# decoupling.net
KiCad netlist of a schematic drawn in Altium Designer
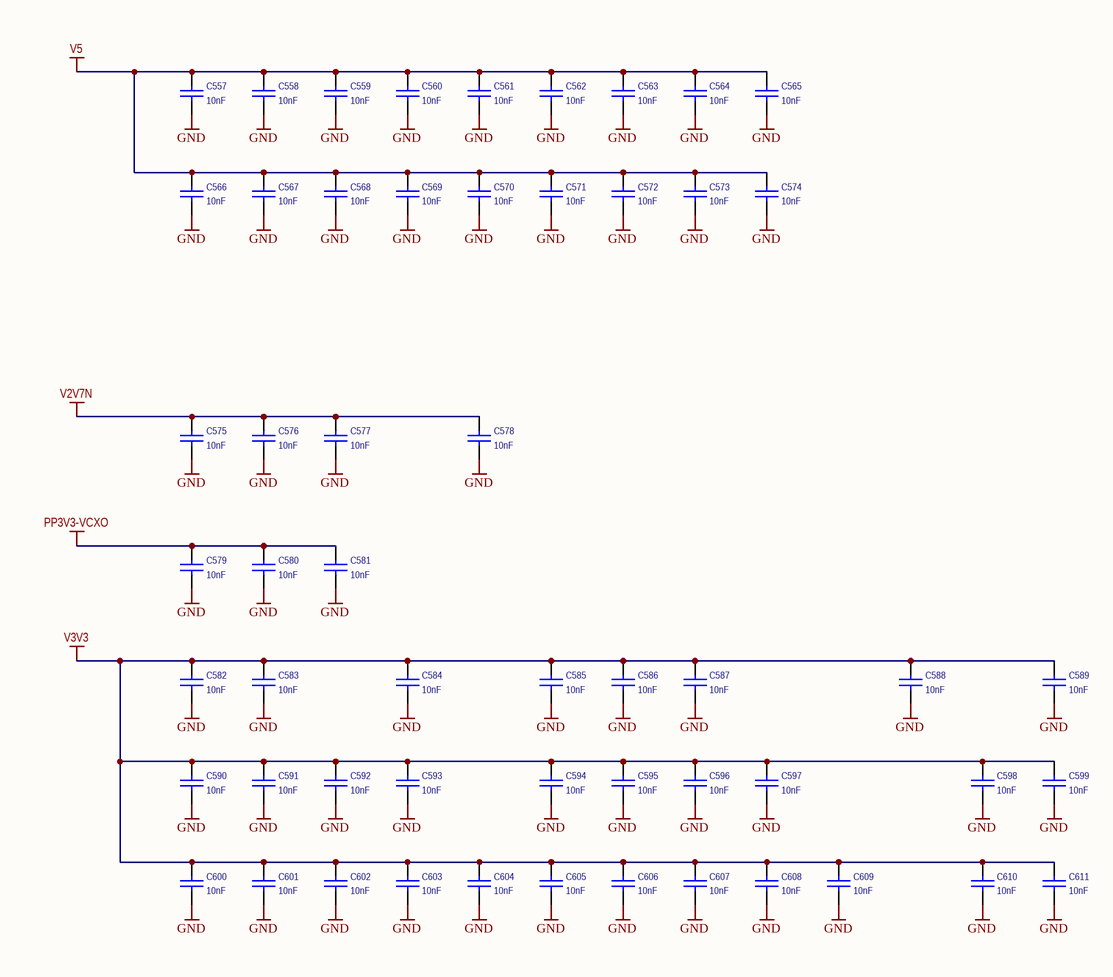
[diagram p0: decoupling.SchDoc]

(export (version "E")
  (design (tool "Eeschema 10.0.6"))
  (components
    (comp (ref "C557")
      (value "10nF")
      (footprint "CAPC100X50X55L25N")
      (description "Ceramic Capacitor 10nF ±10% 50V X7R 0402")
      (fields (field (name "VOLTAGE") "50V") (field (name "MANUFACTURER") "Murata"))
      (libsource (lib "Graviton") (part "CAP 0402"))
    )
    (comp (ref "C558")
      (value "10nF")
      (footprint "CAPC100X50X55L25N")
      (description "Ceramic Capacitor 10nF ±10% 50V X7R 0402")
      (fields (field (name "VOLTAGE") "50V") (field (name "MANUFACTURER") "Murata"))
      (libsource (lib "Graviton") (part "CAP 0402"))
    )
    (comp (ref "C559")
      (value "10nF")
      (footprint "CAPC100X50X55L25N")
      (description "Ceramic Capacitor 10nF ±10% 50V X7R 0402")
      (fields (field (name "VOLTAGE") "50V") (field (name "MANUFACTURER") "Murata"))
      (libsource (lib "Graviton") (part "CAP 0402"))
    )
    (comp (ref "C560")
      (value "10nF")
      (footprint "CAPC100X50X55L25N")
      (description "Ceramic Capacitor 10nF ±10% 50V X7R 0402")
      (fields (field (name "VOLTAGE") "50V") (field (name "MANUFACTURER") "Murata"))
      (libsource (lib "Graviton") (part "CAP 0402"))
    )
    (comp (ref "C561")
      (value "10nF")
      (footprint "CAPC100X50X55L25N")
      (description "Ceramic Capacitor 10nF ±10% 50V X7R 0402")
      (fields (field (name "VOLTAGE") "50V") (field (name "MANUFACTURER") "Murata"))
      (libsource (lib "Graviton") (part "CAP 0402"))
    )
    (comp (ref "C562")
      (value "10nF")
      (footprint "CAPC100X50X55L25N")
      (description "Ceramic Capacitor 10nF ±10% 50V X7R 0402")
      (fields (field (name "VOLTAGE") "50V") (field (name "MANUFACTURER") "Murata"))
      (libsource (lib "Graviton") (part "CAP 0402"))
    )
    (comp (ref "C563")
      (value "10nF")
      (footprint "CAPC100X50X55L25N")
      (description "Ceramic Capacitor 10nF ±10% 50V X7R 0402")
      (fields (field (name "VOLTAGE") "50V") (field (name "MANUFACTURER") "Murata"))
      (libsource (lib "Graviton") (part "CAP 0402"))
    )
    (comp (ref "C564")
      (value "10nF")
      (footprint "CAPC100X50X55L25N")
      (description "Ceramic Capacitor 10nF ±10% 50V X7R 0402")
      (fields (field (name "VOLTAGE") "50V") (field (name "MANUFACTURER") "Murata"))
      (libsource (lib "Graviton") (part "CAP 0402"))
    )
    (comp (ref "C565")
      (value "10nF")
      (footprint "CAPC100X50X55L25N")
      (description "Ceramic Capacitor 10nF ±10% 50V X7R 0402")
      (fields (field (name "VOLTAGE") "50V") (field (name "MANUFACTURER") "Murata"))
      (libsource (lib "Graviton") (part "CAP 0402"))
    )
    (comp (ref "C566")
      (value "10nF")
      (footprint "CAPC100X50X55L25N")
      (description "Ceramic Capacitor 10nF ±10% 50V X7R 0402")
      (fields (field (name "VOLTAGE") "50V") (field (name "MANUFACTURER") "Murata"))
      (libsource (lib "Graviton") (part "CAP 0402"))
    )
    (comp (ref "C567")
      (value "10nF")
      (footprint "CAPC100X50X55L25N")
      (description "Ceramic Capacitor 10nF ±10% 50V X7R 0402")
      (fields (field (name "VOLTAGE") "50V") (field (name "MANUFACTURER") "Murata"))
      (libsource (lib "Graviton") (part "CAP 0402"))
    )
    (comp (ref "C568")
      (value "10nF")
      (footprint "CAPC100X50X55L25N")
      (description "Ceramic Capacitor 10nF ±10% 50V X7R 0402")
      (fields (field (name "VOLTAGE") "50V") (field (name "MANUFACTURER") "Murata"))
      (libsource (lib "Graviton") (part "CAP 0402"))
    )
    (comp (ref "C569")
      (value "10nF")
      (footprint "CAPC100X50X55L25N")
      (description "Ceramic Capacitor 10nF ±10% 50V X7R 0402")
      (fields (field (name "VOLTAGE") "50V") (field (name "MANUFACTURER") "Murata"))
      (libsource (lib "Graviton") (part "CAP 0402"))
    )
    (comp (ref "C570")
      (value "10nF")
      (footprint "CAPC100X50X55L25N")
      (description "Ceramic Capacitor 10nF ±10% 50V X7R 0402")
      (fields (field (name "VOLTAGE") "50V") (field (name "MANUFACTURER") "Murata"))
      (libsource (lib "Graviton") (part "CAP 0402"))
    )
    (comp (ref "C571")
      (value "10nF")
      (footprint "CAPC100X50X55L25N")
      (description "Ceramic Capacitor 10nF ±10% 50V X7R 0402")
      (fields (field (name "VOLTAGE") "50V") (field (name "MANUFACTURER") "Murata"))
      (libsource (lib "Graviton") (part "CAP 0402"))
    )
    (comp (ref "C572")
      (value "10nF")
      (footprint "CAPC100X50X55L25N")
      (description "Ceramic Capacitor 10nF ±10% 50V X7R 0402")
      (fields (field (name "VOLTAGE") "50V") (field (name "MANUFACTURER") "Murata"))
      (libsource (lib "Graviton") (part "CAP 0402"))
    )
    (comp (ref "C573")
      (value "10nF")
      (footprint "CAPC100X50X55L25N")
      (description "Ceramic Capacitor 10nF ±10% 50V X7R 0402")
      (fields (field (name "VOLTAGE") "50V") (field (name "MANUFACTURER") "Murata"))
      (libsource (lib "Graviton") (part "CAP 0402"))
    )
    (comp (ref "C574")
      (value "10nF")
      (footprint "CAPC100X50X55L25N")
      (description "Ceramic Capacitor 10nF ±10% 50V X7R 0402")
      (fields (field (name "VOLTAGE") "50V") (field (name "MANUFACTURER") "Murata"))
      (libsource (lib "Graviton") (part "CAP 0402"))
    )
    (comp (ref "C575")
      (value "10nF")
      (footprint "CAPC100X50X55L25N")
      (description "Ceramic Capacitor 10nF ±10% 50V X7R 0402")
      (fields (field (name "VOLTAGE") "50V") (field (name "MANUFACTURER") "Murata"))
      (libsource (lib "Graviton") (part "CAP 0402"))
    )
    (comp (ref "C576")
      (value "10nF")
      (footprint "CAPC100X50X55L25N")
      (description "Ceramic Capacitor 10nF ±10% 50V X7R 0402")
      (fields (field (name "VOLTAGE") "50V") (field (name "MANUFACTURER") "Murata"))
      (libsource (lib "Graviton") (part "CAP 0402"))
    )
    (comp (ref "C577")
      (value "10nF")
      (footprint "CAPC100X50X55L25N")
      (description "Ceramic Capacitor 10nF ±10% 50V X7R 0402")
      (fields (field (name "VOLTAGE") "50V") (field (name "MANUFACTURER") "Murata"))
      (libsource (lib "Graviton") (part "CAP 0402"))
    )
    (comp (ref "C578")
      (value "10nF")
      (footprint "CAPC100X50X55L25N")
      (description "Ceramic Capacitor 10nF ±10% 50V X7R 0402")
      (fields (field (name "VOLTAGE") "50V") (field (name "MANUFACTURER") "Murata"))
      (libsource (lib "Graviton") (part "CAP 0402"))
    )
    (comp (ref "C579")
      (value "10nF")
      (footprint "CAPC100X50X55L25N")
      (description "Ceramic Capacitor 10nF ±10% 50V X7R 0402")
      (fields (field (name "VOLTAGE") "50V") (field (name "MANUFACTURER") "Murata"))
      (libsource (lib "Graviton") (part "CAP 0402"))
    )
    (comp (ref "C580")
      (value "10nF")
      (footprint "CAPC100X50X55L25N")
      (description "Ceramic Capacitor 10nF ±10% 50V X7R 0402")
      (fields (field (name "VOLTAGE") "50V") (field (name "MANUFACTURER") "Murata"))
      (libsource (lib "Graviton") (part "CAP 0402"))
    )
    (comp (ref "C581")
      (value "10nF")
      (footprint "CAPC100X50X55L25N")
      (description "Ceramic Capacitor 10nF ±10% 50V X7R 0402")
      (fields (field (name "VOLTAGE") "50V") (field (name "MANUFACTURER") "Murata"))
      (libsource (lib "Graviton") (part "CAP 0402"))
    )
    (comp (ref "C582")
      (value "10nF")
      (footprint "CAPC100X50X55L25N")
      (description "Ceramic Capacitor 10nF ±10% 50V X7R 0402")
      (fields (field (name "VOLTAGE") "50V") (field (name "MANUFACTURER") "Murata"))
      (libsource (lib "Graviton") (part "CAP 0402"))
    )
    (comp (ref "C583")
      (value "10nF")
      (footprint "CAPC100X50X55L25N")
      (description "Ceramic Capacitor 10nF ±10% 50V X7R 0402")
      (fields (field (name "VOLTAGE") "50V") (field (name "MANUFACTURER") "Murata"))
      (libsource (lib "Graviton") (part "CAP 0402"))
    )
    (comp (ref "C584")
      (value "10nF")
      (footprint "CAPC100X50X55L25N")
      (description "Ceramic Capacitor 10nF ±10% 50V X7R 0402")
      (fields (field (name "VOLTAGE") "50V") (field (name "MANUFACTURER") "Murata"))
      (libsource (lib "Graviton") (part "CAP 0402"))
    )
    (comp (ref "C585")
      (value "10nF")
      (footprint "CAPC100X50X55L25N")
      (description "Ceramic Capacitor 10nF ±10% 50V X7R 0402")
      (fields (field (name "VOLTAGE") "50V") (field (name "MANUFACTURER") "Murata"))
      (libsource (lib "Graviton") (part "CAP 0402"))
    )
    (comp (ref "C586")
      (value "10nF")
      (footprint "CAPC100X50X55L25N")
      (description "Ceramic Capacitor 10nF ±10% 50V X7R 0402")
      (fields (field (name "VOLTAGE") "50V") (field (name "MANUFACTURER") "Murata"))
      (libsource (lib "Graviton") (part "CAP 0402"))
    )
    (comp (ref "C587")
      (value "10nF")
      (footprint "CAPC100X50X55L25N")
      (description "Ceramic Capacitor 10nF ±10% 50V X7R 0402")
      (fields (field (name "VOLTAGE") "50V") (field (name "MANUFACTURER") "Murata"))
      (libsource (lib "Graviton") (part "CAP 0402"))
    )
    (comp (ref "C588")
      (value "10nF")
      (footprint "CAPC100X50X55L25N")
      (description "Ceramic Capacitor 10nF ±10% 50V X7R 0402")
      (fields (field (name "VOLTAGE") "50V") (field (name "MANUFACTURER") "Murata"))
      (libsource (lib "Graviton") (part "CAP 0402"))
    )
    (comp (ref "C589")
      (value "10nF")
      (footprint "CAPC100X50X55L25N")
      (description "Ceramic Capacitor 10nF ±10% 50V X7R 0402")
      (fields (field (name "VOLTAGE") "50V") (field (name "MANUFACTURER") "Murata"))
      (libsource (lib "Graviton") (part "CAP 0402"))
    )
    (comp (ref "C590")
      (value "10nF")
      (footprint "CAPC100X50X55L25N")
      (description "Ceramic Capacitor 10nF ±10% 50V X7R 0402")
      (fields (field (name "VOLTAGE") "50V") (field (name "MANUFACTURER") "Murata"))
      (libsource (lib "Graviton") (part "CAP 0402"))
    )
    (comp (ref "C591")
      (value "10nF")
      (footprint "CAPC100X50X55L25N")
      (description "Ceramic Capacitor 10nF ±10% 50V X7R 0402")
      (fields (field (name "VOLTAGE") "50V") (field (name "MANUFACTURER") "Murata"))
      (libsource (lib "Graviton") (part "CAP 0402"))
    )
    (comp (ref "C592")
      (value "10nF")
      (footprint "CAPC100X50X55L25N")
      (description "Ceramic Capacitor 10nF ±10% 50V X7R 0402")
      (fields (field (name "VOLTAGE") "50V") (field (name "MANUFACTURER") "Murata"))
      (libsource (lib "Graviton") (part "CAP 0402"))
    )
    (comp (ref "C593")
      (value "10nF")
      (footprint "CAPC100X50X55L25N")
      (description "Ceramic Capacitor 10nF ±10% 50V X7R 0402")
      (fields (field (name "VOLTAGE") "50V") (field (name "MANUFACTURER") "Murata"))
      (libsource (lib "Graviton") (part "CAP 0402"))
    )
    (comp (ref "C594")
      (value "10nF")
      (footprint "CAPC100X50X55L25N")
      (description "Ceramic Capacitor 10nF ±10% 50V X7R 0402")
      (fields (field (name "VOLTAGE") "50V") (field (name "MANUFACTURER") "Murata"))
      (libsource (lib "Graviton") (part "CAP 0402"))
    )
    (comp (ref "C595")
      (value "10nF")
      (footprint "CAPC100X50X55L25N")
      (description "Ceramic Capacitor 10nF ±10% 50V X7R 0402")
      (fields (field (name "VOLTAGE") "50V") (field (name "MANUFACTURER") "Murata"))
      (libsource (lib "Graviton") (part "CAP 0402"))
    )
    (comp (ref "C596")
      (value "10nF")
      (footprint "CAPC100X50X55L25N")
      (description "Ceramic Capacitor 10nF ±10% 50V X7R 0402")
      (fields (field (name "VOLTAGE") "50V") (field (name "MANUFACTURER") "Murata"))
      (libsource (lib "Graviton") (part "CAP 0402"))
    )
    (comp (ref "C597")
      (value "10nF")
      (footprint "CAPC100X50X55L25N")
      (description "Ceramic Capacitor 10nF ±10% 50V X7R 0402")
      (fields (field (name "VOLTAGE") "50V") (field (name "MANUFACTURER") "Murata"))
      (libsource (lib "Graviton") (part "CAP 0402"))
    )
    (comp (ref "C598")
      (value "10nF")
      (footprint "CAPC100X50X55L25N")
      (description "Ceramic Capacitor 10nF ±10% 50V X7R 0402")
      (fields (field (name "VOLTAGE") "50V") (field (name "MANUFACTURER") "Murata"))
      (libsource (lib "Graviton") (part "CAP 0402"))
    )
    (comp (ref "C599")
      (value "10nF")
      (footprint "CAPC100X50X55L25N")
      (description "Ceramic Capacitor 10nF ±10% 50V X7R 0402")
      (fields (field (name "VOLTAGE") "50V") (field (name "MANUFACTURER") "Murata"))
      (libsource (lib "Graviton") (part "CAP 0402"))
    )
    (comp (ref "C600")
      (value "10nF")
      (footprint "CAPC100X50X55L25N")
      (description "Ceramic Capacitor 10nF ±10% 50V X7R 0402")
      (fields (field (name "VOLTAGE") "50V") (field (name "MANUFACTURER") "Murata"))
      (libsource (lib "Graviton") (part "CAP 0402"))
    )
    (comp (ref "C601")
      (value "10nF")
      (footprint "CAPC100X50X55L25N")
      (description "Ceramic Capacitor 10nF ±10% 50V X7R 0402")
      (fields (field (name "VOLTAGE") "50V") (field (name "MANUFACTURER") "Murata"))
      (libsource (lib "Graviton") (part "CAP 0402"))
    )
    (comp (ref "C602")
      (value "10nF")
      (footprint "CAPC100X50X55L25N")
      (description "Ceramic Capacitor 10nF ±10% 50V X7R 0402")
      (fields (field (name "VOLTAGE") "50V") (field (name "MANUFACTURER") "Murata"))
      (libsource (lib "Graviton") (part "CAP 0402"))
    )
    (comp (ref "C603")
      (value "10nF")
      (footprint "CAPC100X50X55L25N")
      (description "Ceramic Capacitor 10nF ±10% 50V X7R 0402")
      (fields (field (name "VOLTAGE") "50V") (field (name "MANUFACTURER") "Murata"))
      (libsource (lib "Graviton") (part "CAP 0402"))
    )
    (comp (ref "C604")
      (value "10nF")
      (footprint "CAPC100X50X55L25N")
      (description "Ceramic Capacitor 10nF ±10% 50V X7R 0402")
      (fields (field (name "VOLTAGE") "50V") (field (name "MANUFACTURER") "Murata"))
      (libsource (lib "Graviton") (part "CAP 0402"))
    )
    (comp (ref "C605")
      (value "10nF")
      (footprint "CAPC100X50X55L25N")
      (description "Ceramic Capacitor 10nF ±10% 50V X7R 0402")
      (fields (field (name "VOLTAGE") "50V") (field (name "MANUFACTURER") "Murata"))
      (libsource (lib "Graviton") (part "CAP 0402"))
    )
    (comp (ref "C606")
      (value "10nF")
      (footprint "CAPC100X50X55L25N")
      (description "Ceramic Capacitor 10nF ±10% 50V X7R 0402")
      (fields (field (name "VOLTAGE") "50V") (field (name "MANUFACTURER") "Murata"))
      (libsource (lib "Graviton") (part "CAP 0402"))
    )
    (comp (ref "C607")
      (value "10nF")
      (footprint "CAPC100X50X55L25N")
      (description "Ceramic Capacitor 10nF ±10% 50V X7R 0402")
      (fields (field (name "VOLTAGE") "50V") (field (name "MANUFACTURER") "Murata"))
      (libsource (lib "Graviton") (part "CAP 0402"))
    )
    (comp (ref "C608")
      (value "10nF")
      (footprint "CAPC100X50X55L25N")
      (description "Ceramic Capacitor 10nF ±10% 50V X7R 0402")
      (fields (field (name "VOLTAGE") "50V") (field (name "MANUFACTURER") "Murata"))
      (libsource (lib "Graviton") (part "CAP 0402"))
    )
    (comp (ref "C609")
      (value "10nF")
      (footprint "CAPC100X50X55L25N")
      (description "Ceramic Capacitor 10nF ±10% 50V X7R 0402")
      (fields (field (name "VOLTAGE") "50V") (field (name "MANUFACTURER") "Murata"))
      (libsource (lib "Graviton") (part "CAP 0402"))
    )
    (comp (ref "C610")
      (value "10nF")
      (footprint "CAPC100X50X55L25N")
      (description "Ceramic Capacitor 10nF ±10% 50V X7R 0402")
      (fields (field (name "VOLTAGE") "50V") (field (name "MANUFACTURER") "Murata"))
      (libsource (lib "Graviton") (part "CAP 0402"))
    )
    (comp (ref "C611")
      (value "10nF")
      (footprint "CAPC100X50X55L25N")
      (description "Ceramic Capacitor 10nF ±10% 50V X7R 0402")
      (fields (field (name "VOLTAGE") "50V") (field (name "MANUFACTURER") "Murata"))
      (libsource (lib "Graviton") (part "CAP 0402"))
    )
  )
  (nets
    (net (code "1") (name "GND") (class "Default")
      (node (ref "C557") (pin "1") (pinfunction "1_1") (pintype "passive"))
      (node (ref "C558") (pin "1") (pinfunction "1_1") (pintype "passive"))
      (node (ref "C559") (pin "1") (pinfunction "1_1") (pintype "passive"))
      (node (ref "C560") (pin "1") (pinfunction "1_1") (pintype "passive"))
      (node (ref "C561") (pin "1") (pinfunction "1_1") (pintype "passive"))
      (node (ref "C562") (pin "1") (pinfunction "1_1") (pintype "passive"))
      (node (ref "C563") (pin "1") (pinfunction "1_1") (pintype "passive"))
      (node (ref "C564") (pin "1") (pinfunction "1_1") (pintype "passive"))
      (node (ref "C565") (pin "1") (pinfunction "1_1") (pintype "passive"))
      (node (ref "C566") (pin "1") (pinfunction "1_1") (pintype "passive"))
      (node (ref "C567") (pin "1") (pinfunction "1_1") (pintype "passive"))
      (node (ref "C568") (pin "1") (pinfunction "1_1") (pintype "passive"))
      (node (ref "C569") (pin "1") (pinfunction "1_1") (pintype "passive"))
      (node (ref "C570") (pin "1") (pinfunction "1_1") (pintype "passive"))
      (node (ref "C571") (pin "1") (pinfunction "1_1") (pintype "passive"))
      (node (ref "C572") (pin "1") (pinfunction "1_1") (pintype "passive"))
      (node (ref "C573") (pin "1") (pinfunction "1_1") (pintype "passive"))
      (node (ref "C574") (pin "1") (pinfunction "1_1") (pintype "passive"))
      (node (ref "C575") (pin "1") (pinfunction "1_1") (pintype "passive"))
      (node (ref "C576") (pin "1") (pinfunction "1_1") (pintype "passive"))
      (node (ref "C577") (pin "1") (pinfunction "1_1") (pintype "passive"))
      (node (ref "C578") (pin "1") (pinfunction "1_1") (pintype "passive"))
      (node (ref "C579") (pin "1") (pinfunction "1_1") (pintype "passive"))
      (node (ref "C580") (pin "1") (pinfunction "1_1") (pintype "passive"))
      (node (ref "C581") (pin "1") (pinfunction "1_1") (pintype "passive"))
      (node (ref "C582") (pin "1") (pinfunction "1_1") (pintype "passive"))
      (node (ref "C583") (pin "1") (pinfunction "1_1") (pintype "passive"))
      (node (ref "C584") (pin "1") (pinfunction "1_1") (pintype "passive"))
      (node (ref "C585") (pin "1") (pinfunction "1_1") (pintype "passive"))
      (node (ref "C586") (pin "1") (pinfunction "1_1") (pintype "passive"))
      (node (ref "C587") (pin "1") (pinfunction "1_1") (pintype "passive"))
      (node (ref "C588") (pin "1") (pinfunction "1_1") (pintype "passive"))
      (node (ref "C589") (pin "1") (pinfunction "1_1") (pintype "passive"))
      (node (ref "C590") (pin "1") (pinfunction "1_1") (pintype "passive"))
      (node (ref "C591") (pin "1") (pinfunction "1_1") (pintype "passive"))
      (node (ref "C592") (pin "1") (pinfunction "1_1") (pintype "passive"))
      (node (ref "C593") (pin "1") (pinfunction "1_1") (pintype "passive"))
      (node (ref "C594") (pin "1") (pinfunction "1_1") (pintype "passive"))
      (node (ref "C595") (pin "1") (pinfunction "1_1") (pintype "passive"))
      (node (ref "C596") (pin "1") (pinfunction "1_1") (pintype "passive"))
      (node (ref "C597") (pin "1") (pinfunction "1_1") (pintype "passive"))
      (node (ref "C598") (pin "1") (pinfunction "1_1") (pintype "passive"))
      (node (ref "C599") (pin "1") (pinfunction "1_1") (pintype "passive"))
      (node (ref "C600") (pin "1") (pinfunction "1_1") (pintype "passive"))
      (node (ref "C601") (pin "1") (pinfunction "1_1") (pintype "passive"))
      (node (ref "C602") (pin "1") (pinfunction "1_1") (pintype "passive"))
      (node (ref "C603") (pin "1") (pinfunction "1_1") (pintype "passive"))
      (node (ref "C604") (pin "1") (pinfunction "1_1") (pintype "passive"))
      (node (ref "C605") (pin "1") (pinfunction "1_1") (pintype "passive"))
      (node (ref "C606") (pin "1") (pinfunction "1_1") (pintype "passive"))
      (node (ref "C607") (pin "1") (pinfunction "1_1") (pintype "passive"))
      (node (ref "C608") (pin "1") (pinfunction "1_1") (pintype "passive"))
      (node (ref "C609") (pin "1") (pinfunction "1_1") (pintype "passive"))
      (node (ref "C610") (pin "1") (pinfunction "1_1") (pintype "passive"))
      (node (ref "C611") (pin "1") (pinfunction "1_1") (pintype "passive"))
    )
    (net (code "2") (name "PP3V3-VCXO") (class "Default")
      (node (ref "C579") (pin "2") (pinfunction "2_2") (pintype "passive"))
      (node (ref "C580") (pin "2") (pinfunction "2_2") (pintype "passive"))
      (node (ref "C581") (pin "2") (pinfunction "2_2") (pintype "passive"))
    )
    (net (code "3") (name "V2V7N") (class "Default")
      (node (ref "C575") (pin "2") (pinfunction "2_2") (pintype "passive"))
      (node (ref "C576") (pin "2") (pinfunction "2_2") (pintype "passive"))
      (node (ref "C577") (pin "2") (pinfunction "2_2") (pintype "passive"))
      (node (ref "C578") (pin "2") (pinfunction "2_2") (pintype "passive"))
    )
    (net (code "4") (name "V3V3") (class "Default")
      (node (ref "C582") (pin "2") (pinfunction "2_2") (pintype "passive"))
      (node (ref "C583") (pin "2") (pinfunction "2_2") (pintype "passive"))
      (node (ref "C584") (pin "2") (pinfunction "2_2") (pintype "passive"))
      (node (ref "C585") (pin "2") (pinfunction "2_2") (pintype "passive"))
      (node (ref "C586") (pin "2") (pinfunction "2_2") (pintype "passive"))
      (node (ref "C587") (pin "2") (pinfunction "2_2") (pintype "passive"))
      (node (ref "C588") (pin "2") (pinfunction "2_2") (pintype "passive"))
      (node (ref "C589") (pin "2") (pinfunction "2_2") (pintype "passive"))
      (node (ref "C590") (pin "2") (pinfunction "2_2") (pintype "passive"))
      (node (ref "C591") (pin "2") (pinfunction "2_2") (pintype "passive"))
      (node (ref "C592") (pin "2") (pinfunction "2_2") (pintype "passive"))
      (node (ref "C593") (pin "2") (pinfunction "2_2") (pintype "passive"))
      (node (ref "C594") (pin "2") (pinfunction "2_2") (pintype "passive"))
      (node (ref "C595") (pin "2") (pinfunction "2_2") (pintype "passive"))
      (node (ref "C596") (pin "2") (pinfunction "2_2") (pintype "passive"))
      (node (ref "C597") (pin "2") (pinfunction "2_2") (pintype "passive"))
      (node (ref "C598") (pin "2") (pinfunction "2_2") (pintype "passive"))
      (node (ref "C599") (pin "2") (pinfunction "2_2") (pintype "passive"))
      (node (ref "C600") (pin "2") (pinfunction "2_2") (pintype "passive"))
      (node (ref "C601") (pin "2") (pinfunction "2_2") (pintype "passive"))
      (node (ref "C602") (pin "2") (pinfunction "2_2") (pintype "passive"))
      (node (ref "C603") (pin "2") (pinfunction "2_2") (pintype "passive"))
      (node (ref "C604") (pin "2") (pinfunction "2_2") (pintype "passive"))
      (node (ref "C605") (pin "2") (pinfunction "2_2") (pintype "passive"))
      (node (ref "C606") (pin "2") (pinfunction "2_2") (pintype "passive"))
      (node (ref "C607") (pin "2") (pinfunction "2_2") (pintype "passive"))
      (node (ref "C608") (pin "2") (pinfunction "2_2") (pintype "passive"))
      (node (ref "C609") (pin "2") (pinfunction "2_2") (pintype "passive"))
      (node (ref "C610") (pin "2") (pinfunction "2_2") (pintype "passive"))
      (node (ref "C611") (pin "2") (pinfunction "2_2") (pintype "passive"))
    )
    (net (code "5") (name "V5") (class "Default")
      (node (ref "C557") (pin "2") (pinfunction "2_2") (pintype "passive"))
      (node (ref "C558") (pin "2") (pinfunction "2_2") (pintype "passive"))
      (node (ref "C559") (pin "2") (pinfunction "2_2") (pintype "passive"))
      (node (ref "C560") (pin "2") (pinfunction "2_2") (pintype "passive"))
      (node (ref "C561") (pin "2") (pinfunction "2_2") (pintype "passive"))
      (node (ref "C562") (pin "2") (pinfunction "2_2") (pintype "passive"))
      (node (ref "C563") (pin "2") (pinfunction "2_2") (pintype "passive"))
      (node (ref "C564") (pin "2") (pinfunction "2_2") (pintype "passive"))
      (node (ref "C565") (pin "2") (pinfunction "2_2") (pintype "passive"))
      (node (ref "C566") (pin "2") (pinfunction "2_2") (pintype "passive"))
      (node (ref "C567") (pin "2") (pinfunction "2_2") (pintype "passive"))
      (node (ref "C568") (pin "2") (pinfunction "2_2") (pintype "passive"))
      (node (ref "C569") (pin "2") (pinfunction "2_2") (pintype "passive"))
      (node (ref "C570") (pin "2") (pinfunction "2_2") (pintype "passive"))
      (node (ref "C571") (pin "2") (pinfunction "2_2") (pintype "passive"))
      (node (ref "C572") (pin "2") (pinfunction "2_2") (pintype "passive"))
      (node (ref "C573") (pin "2") (pinfunction "2_2") (pintype "passive"))
      (node (ref "C574") (pin "2") (pinfunction "2_2") (pintype "passive"))
    )
  )
)
